# dedo_rev_1_2.net
KiCad netlist of a schematic drawn in EAGLE
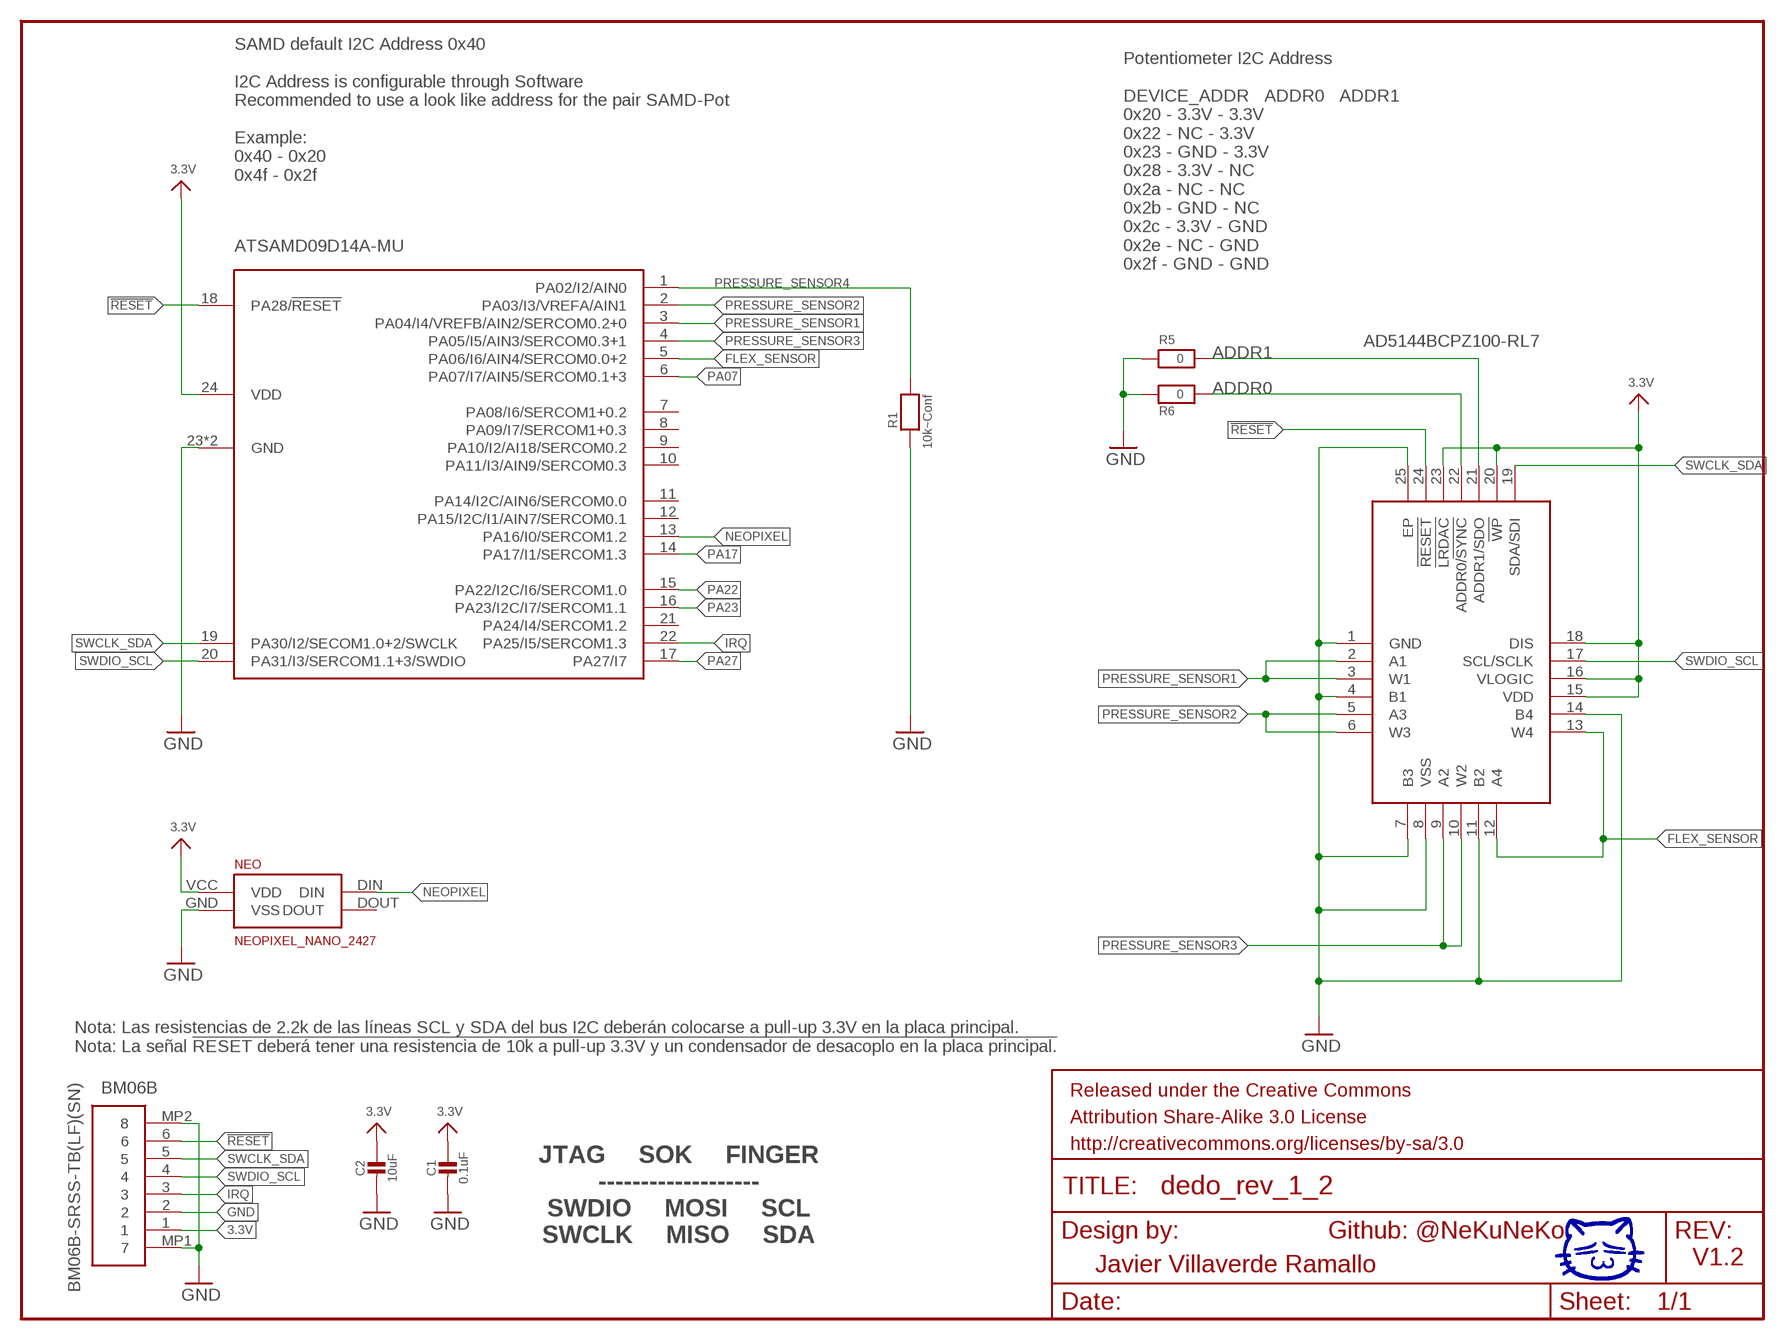
[diagram p0: schematic, sheet 1]

(export (version "E")
  (design (tool "Eeschema 10.0.6"))
  (components
    (comp (ref "AD5144BCPZ100")
      (value "AD5144BCPZ100-RL7")
      (footprint "eagle-import:QFN50P400X400X80-25N")
      (fields (field (name "MOUSER_PART_NUMBER") "584-AD5144BCPZ100-R7"))
      (libsource (lib "eagle-import") (part "AD5144BCPZ100-RL7"))
    )
    (comp (ref "BM06B")
      (value "BM06B-SRSS-TB(LF)(SN)")
      (footprint "eagle-import:BM06BSRSSTBLFSN")
      (fields (field (name "RS_PART_NUMBER") "5468782"))
      (libsource (lib "eagle-import") (part "BM06B-SRSS-TB(LF)(SN)"))
    )
    (comp (ref "C1")
      (value "0.1uF")
      (footprint "eagle-import:0402")
      (libsource (lib "eagle-import") (part "CAP_CERAMIC0402"))
    )
    (comp (ref "C2")
      (value "10uF")
      (footprint "eagle-import:0402")
      (libsource (lib "eagle-import") (part "CAP_CERAMIC0402"))
    )
    (comp (ref "FRAME1")
      (value "FRAME-LETTER")
      (footprint "eagle-import:CREATIVE_COMMONS")
      (libsource (lib "eagle-import") (part "FRAME-LETTER"))
    )
    (comp (ref "FRAME2")
      (value "FRAME-LETTER")
      (footprint "eagle-import:CREATIVE_COMMONS")
      (libsource (lib "eagle-import") (part "FRAME-LETTER"))
    )
    (comp (ref "NEO")
      (value "NEOPIXEL_NANO_2427")
      (footprint "eagle-import:SK6805-2427")
      (libsource (lib "eagle-import") (part "NEOPIXEL_NANO_2427"))
    )
    (comp (ref "R1")
      (value "10k~Conf")
      (footprint "eagle-import:_0402")
      (libsource (lib "eagle-import") (part "RESISTOR_0402"))
    )
    (comp (ref "R5")
      (value "0")
      (footprint "eagle-import:_0402")
      (libsource (lib "eagle-import") (part "RESISTOR_0402"))
    )
    (comp (ref "R6")
      (value "0")
      (footprint "eagle-import:_0402")
      (libsource (lib "eagle-import") (part "RESISTOR_0402"))
    )
    (comp (ref "SAMD09")
      (value "ATSAMD09D14A-MU")
      (footprint "eagle-import:QFN24_4MM")
      (libsource (lib "eagle-import") (part "ATSAMD09D14A-MU"))
    )
  )
  (nets
    (net (code "1") (name "/ADDR0") (class "Default")
      (node (ref "AD5144BCPZ100") (pin "22") (pinfunction "ADDR0/~{SYNC}_22") (pintype "bidirectional"))
      (node (ref "R6") (pin "2") (pinfunction "2_2") (pintype "passive"))
    )
    (net (code "2") (name "/ADDR1") (class "Default")
      (node (ref "AD5144BCPZ100") (pin "21") (pinfunction "ADDR1/SDO_21") (pintype "bidirectional"))
      (node (ref "R5") (pin "2") (pinfunction "2_2") (pintype "passive"))
    )
    (net (code "3") (name "/PRESSURE_SENSOR4") (class "Default")
      (node (ref "R1") (pin "1") (pinfunction "1_1") (pintype "passive"))
      (node (ref "SAMD09") (pin "1") (pinfunction "PA02/I2/AIN0_1") (pintype "bidirectional"))
    )
    (net (code "4") (name "/~{RESET}") (class "Default")
      (node (ref "AD5144BCPZ100") (pin "24") (pinfunction "~{RESET}_24") (pintype "bidirectional"))
      (node (ref "BM06B") (pin "6") (pinfunction "6_6") (pintype "bidirectional"))
      (node (ref "SAMD09") (pin "18") (pinfunction "PA28/~{RESET}_18") (pintype "bidirectional"))
    )
    (net (code "5") (name "3.3V") (class "Default")
      (node (ref "AD5144BCPZ100") (pin "15") (pinfunction "VDD_15") (pintype "bidirectional"))
      (node (ref "AD5144BCPZ100") (pin "16") (pinfunction "VLOGIC_16") (pintype "bidirectional"))
      (node (ref "AD5144BCPZ100") (pin "18") (pinfunction "DIS_18") (pintype "bidirectional"))
      (node (ref "AD5144BCPZ100") (pin "20") (pinfunction "~{WP}_20") (pintype "bidirectional"))
      (node (ref "AD5144BCPZ100") (pin "23") (pinfunction "~{LRDAC}_23") (pintype "bidirectional"))
      (node (ref "BM06B") (pin "1") (pinfunction "1_1") (pintype "bidirectional"))
      (node (ref "C1") (pin "1") (pinfunction "P$1_1") (pintype "passive"))
      (node (ref "C2") (pin "1") (pinfunction "P$1_1") (pintype "passive"))
      (node (ref "NEO") (pin "VCC") (pinfunction "VDD_VCC") (pintype "bidirectional"))
      (node (ref "SAMD09") (pin "24") (pinfunction "VDD_24") (pintype "power_in"))
    )
    (net (code "6") (name "FLEX_SENSOR") (class "Default")
      (node (ref "AD5144BCPZ100") (pin "12") (pinfunction "A4_12") (pintype "bidirectional"))
      (node (ref "AD5144BCPZ100") (pin "13") (pinfunction "W4_13") (pintype "bidirectional"))
      (node (ref "SAMD09") (pin "5") (pinfunction "PA06/I6/AIN4/SERCOM0.0+2_5") (pintype "bidirectional"))
    )
    (net (code "7") (name "GND") (class "Default")
      (node (ref "AD5144BCPZ100") (pin "1") (pinfunction "GND_1") (pintype "bidirectional"))
      (node (ref "AD5144BCPZ100") (pin "11") (pinfunction "B2_11") (pintype "bidirectional"))
      (node (ref "AD5144BCPZ100") (pin "14") (pinfunction "B4_14") (pintype "bidirectional"))
      (node (ref "AD5144BCPZ100") (pin "25") (pinfunction "EP_25") (pintype "bidirectional"))
      (node (ref "AD5144BCPZ100") (pin "4") (pinfunction "B1_4") (pintype "bidirectional"))
      (node (ref "AD5144BCPZ100") (pin "7") (pinfunction "B3_7") (pintype "bidirectional"))
      (node (ref "AD5144BCPZ100") (pin "8") (pinfunction "VSS_8") (pintype "bidirectional"))
      (node (ref "BM06B") (pin "2") (pinfunction "2_2") (pintype "bidirectional"))
      (node (ref "BM06B") (pin "MP1") (pinfunction "7_MP1") (pintype "bidirectional"))
      (node (ref "BM06B") (pin "MP2") (pinfunction "8_MP2") (pintype "bidirectional"))
      (node (ref "C1") (pin "2") (pinfunction "P$2_2") (pintype "passive"))
      (node (ref "C2") (pin "2") (pinfunction "P$2_2") (pintype "passive"))
      (node (ref "NEO") (pin "GND") (pinfunction "VSS_GND") (pintype "bidirectional"))
      (node (ref "R1") (pin "2") (pinfunction "2_2") (pintype "passive"))
      (node (ref "R5") (pin "1") (pinfunction "1_1") (pintype "passive"))
      (node (ref "R6") (pin "1") (pinfunction "1_1") (pintype "passive"))
      (node (ref "SAMD09") (pin "23") (pinfunction "GND_23") (pintype "power_in"))
      (node (ref "SAMD09") (pin "THERM") (pinfunction "GND_THERM") (pintype "power_in"))
    )
    (net (code "8") (name "IRQ") (class "Default")
      (node (ref "BM06B") (pin "3") (pinfunction "3_3") (pintype "bidirectional"))
      (node (ref "SAMD09") (pin "22") (pinfunction "PA25/I5/SERCOM1.3_22") (pintype "bidirectional"))
    )
    (net (code "9") (name "NEOPIXEL") (class "Default")
      (node (ref "NEO") (pin "DIN") (pinfunction "DIN_DIN") (pintype "bidirectional"))
      (node (ref "SAMD09") (pin "13") (pinfunction "PA16/I0/SERCOM1.2_13") (pintype "bidirectional"))
    )
    (net (code "10") (name "PA07") (class "Default")
      (node (ref "SAMD09") (pin "6") (pinfunction "PA07/I7/AIN5/SERCOM0.1+3_6") (pintype "bidirectional"))
    )
    (net (code "11") (name "PA17") (class "Default")
      (node (ref "SAMD09") (pin "14") (pinfunction "PA17/I1/SERCOM1.3_14") (pintype "bidirectional"))
    )
    (net (code "12") (name "PA22") (class "Default")
      (node (ref "SAMD09") (pin "15") (pinfunction "PA22/I2C/I6/SERCOM1.0_15") (pintype "bidirectional"))
    )
    (net (code "13") (name "PA23") (class "Default")
      (node (ref "SAMD09") (pin "16") (pinfunction "PA23/I2C/I7/SERCOM1.1_16") (pintype "bidirectional"))
    )
    (net (code "14") (name "PA27") (class "Default")
      (node (ref "SAMD09") (pin "17") (pinfunction "PA27/I7_17") (pintype "bidirectional"))
    )
    (net (code "15") (name "PRESSURE_SENSOR1") (class "Default")
      (node (ref "AD5144BCPZ100") (pin "2") (pinfunction "A1_2") (pintype "bidirectional"))
      (node (ref "AD5144BCPZ100") (pin "3") (pinfunction "W1_3") (pintype "bidirectional"))
      (node (ref "SAMD09") (pin "3") (pinfunction "PA04/I4/VREFB/AIN2/SERCOM0.2+0_3") (pintype "bidirectional"))
    )
    (net (code "16") (name "PRESSURE_SENSOR2") (class "Default")
      (node (ref "AD5144BCPZ100") (pin "5") (pinfunction "A3_5") (pintype "bidirectional"))
      (node (ref "AD5144BCPZ100") (pin "6") (pinfunction "W3_6") (pintype "bidirectional"))
      (node (ref "SAMD09") (pin "2") (pinfunction "PA03/I3/VREFA/AIN1_2") (pintype "bidirectional"))
    )
    (net (code "17") (name "PRESSURE_SENSOR3") (class "Default")
      (node (ref "AD5144BCPZ100") (pin "10") (pinfunction "W2_10") (pintype "bidirectional"))
      (node (ref "AD5144BCPZ100") (pin "9") (pinfunction "A2_9") (pintype "bidirectional"))
      (node (ref "SAMD09") (pin "4") (pinfunction "PA05/I5/AIN3/SERCOM0.3+1_4") (pintype "bidirectional"))
    )
    (net (code "18") (name "SWCLK_SDA") (class "Default")
      (node (ref "AD5144BCPZ100") (pin "19") (pinfunction "SDA/SDI_19") (pintype "bidirectional"))
      (node (ref "BM06B") (pin "5") (pinfunction "5_5") (pintype "bidirectional"))
      (node (ref "SAMD09") (pin "19") (pinfunction "PA30/I2/SECOM1.0+2/SWCLK_19") (pintype "bidirectional"))
    )
    (net (code "19") (name "SWDIO_SCL") (class "Default")
      (node (ref "AD5144BCPZ100") (pin "17") (pinfunction "SCL/SCLK_17") (pintype "bidirectional"))
      (node (ref "BM06B") (pin "4") (pinfunction "4_4") (pintype "bidirectional"))
      (node (ref "SAMD09") (pin "20") (pinfunction "PA31/I3/SERCOM1.1+3/SWDIO_20") (pintype "bidirectional"))
    )
    (net (code "20") (name "unconnected-(NEO-PadDOUT)") (class "Default")
      (node (ref "NEO") (pin "DOUT") (pinfunction "DOUT_DOUT") (pintype "bidirectional"))
    )
    (net (code "21") (name "unconnected-(SAMD09-PA08{slash}I6{slash}SERCOM1+0.2-Pad7)") (class "Default")
      (node (ref "SAMD09") (pin "7") (pinfunction "PA08/I6/SERCOM1+0.2_7") (pintype "bidirectional"))
    )
    (net (code "22") (name "unconnected-(SAMD09-PA09{slash}I7{slash}SERCOM1+0.3-Pad8)") (class "Default")
      (node (ref "SAMD09") (pin "8") (pinfunction "PA09/I7/SERCOM1+0.3_8") (pintype "bidirectional"))
    )
    (net (code "23") (name "unconnected-(SAMD09-PA10{slash}I2{slash}AI18{slash}SERCOM0.2-Pad9)") (class "Default")
      (node (ref "SAMD09") (pin "9") (pinfunction "PA10/I2/AI18/SERCOM0.2_9") (pintype "bidirectional"))
    )
    (net (code "24") (name "unconnected-(SAMD09-PA11{slash}I3{slash}AIN9{slash}SERCOM0.3-Pad10)") (class "Default")
      (node (ref "SAMD09") (pin "10") (pinfunction "PA11/I3/AIN9/SERCOM0.3_10") (pintype "bidirectional"))
    )
    (net (code "25") (name "unconnected-(SAMD09-PA14{slash}I2C{slash}AIN6{slash}SERCOM0.0-Pad11)") (class "Default")
      (node (ref "SAMD09") (pin "11") (pinfunction "PA14/I2C/AIN6/SERCOM0.0_11") (pintype "bidirectional"))
    )
    (net (code "26") (name "unconnected-(SAMD09-PA15{slash}I2C{slash}I1{slash}AIN7{slash}SERCOM0.1-Pad12)") (class "Default")
      (node (ref "SAMD09") (pin "12") (pinfunction "PA15/I2C/I1/AIN7/SERCOM0.1_12") (pintype "bidirectional"))
    )
    (net (code "27") (name "unconnected-(SAMD09-PA24{slash}I4{slash}SERCOM1.2-Pad21)") (class "Default")
      (node (ref "SAMD09") (pin "21") (pinfunction "PA24/I4/SERCOM1.2_21") (pintype "bidirectional"))
    )
  )
)
